# Sensors.net
KiCad netlist of a schematic drawn in Altium Designer
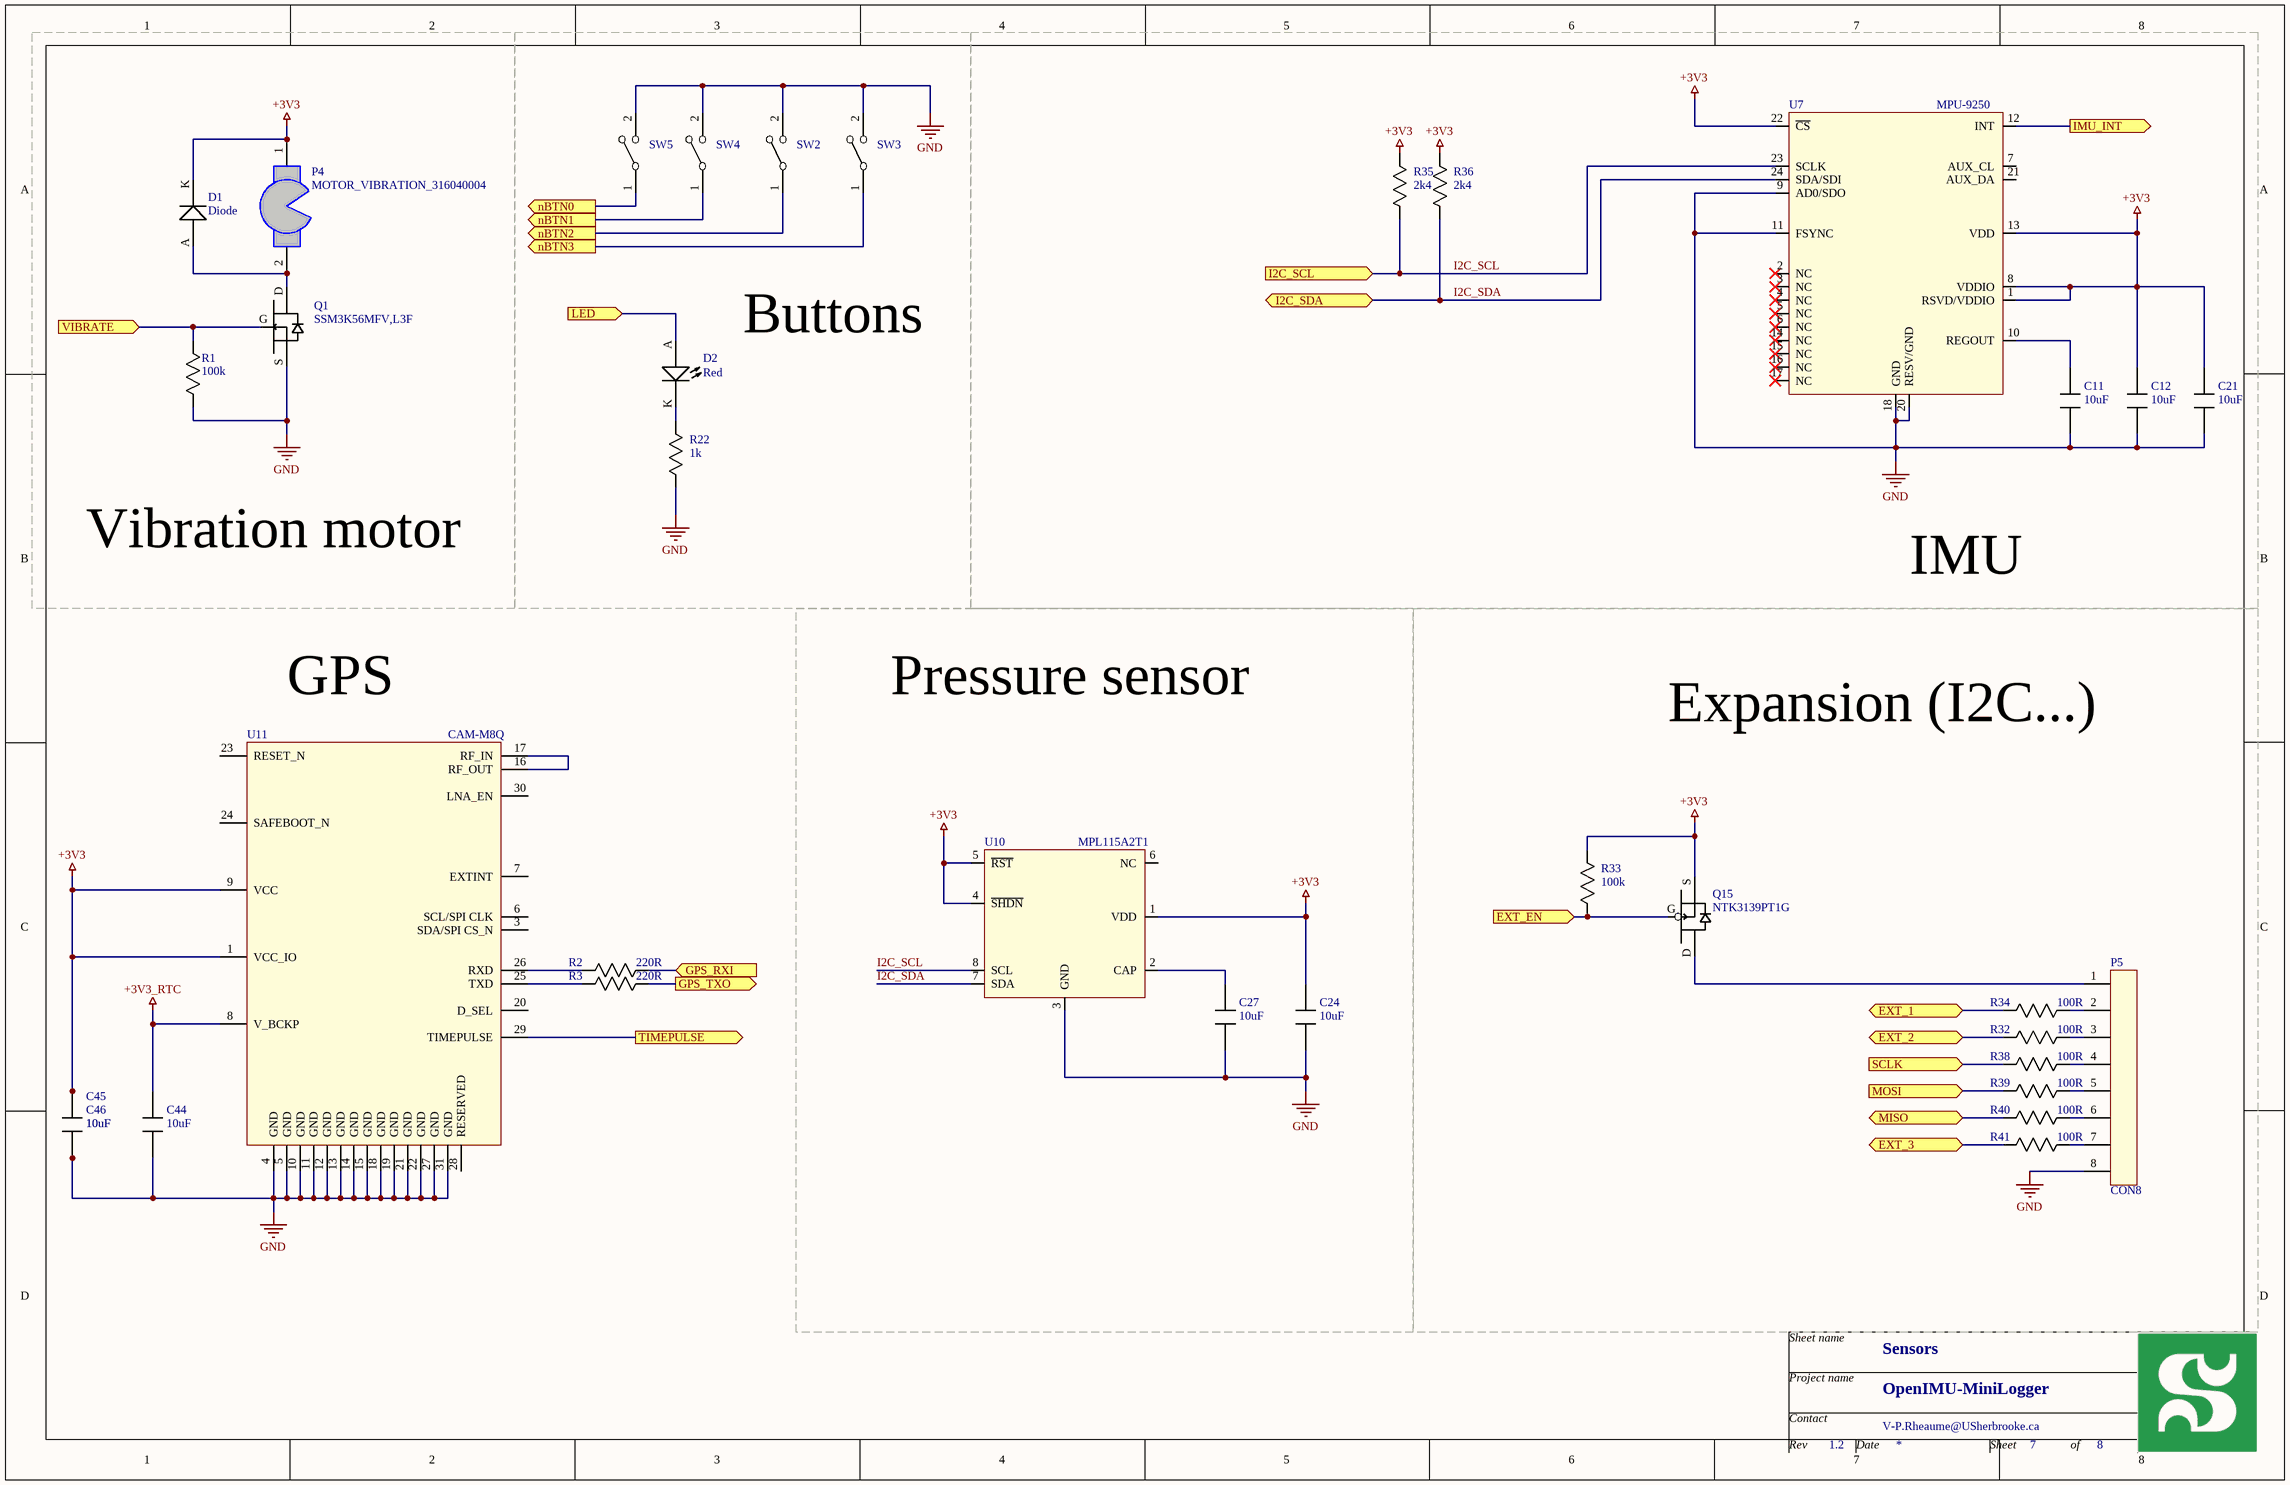
[diagram p0: Sensors.SchDoc]

(export (version "E")
  (design (tool "Eeschema 10.0.6"))
  (components
    (comp (ref "C11")
      (value "10uF")
      (footprint "0603")
      (description "Capacitor")
      (fields (field (name "MFG") "Murata"))
      (libsource (lib "INTER_2014") (part "Capacitor"))
    )
    (comp (ref "C12")
      (value "10uF")
      (footprint "0603")
      (description "Capacitor")
      (fields (field (name "MFG") "Murata"))
      (libsource (lib "INTER_2014") (part "Capacitor"))
    )
    (comp (ref "C21")
      (value "10uF")
      (footprint "0603")
      (description "Capacitor")
      (fields (field (name "MFG") "Murata"))
      (libsource (lib "INTER_2014") (part "Capacitor"))
    )
    (comp (ref "C24")
      (value "10uF")
      (footprint "0603")
      (description "Capacitor")
      (fields (field (name "MFG") "Murata"))
      (libsource (lib "INTER_2014") (part "Capacitor"))
    )
    (comp (ref "C27")
      (value "10uF")
      (footprint "0603")
      (description "Capacitor")
      (fields (field (name "MFG") "Murata"))
      (libsource (lib "INTER_2014") (part "Capacitor"))
    )
    (comp (ref "C44")
      (value "10uF")
      (footprint "0603")
      (description "Capacitor")
      (fields (field (name "MFG") "Murata"))
      (libsource (lib "INTER_2014") (part "Capacitor"))
    )
    (comp (ref "C45")
      (value "10uF")
      (footprint "0603")
      (description "Capacitor")
      (fields (field (name "MFG") "Murata"))
      (libsource (lib "INTER_2014") (part "Capacitor"))
    )
    (comp (ref "C46")
      (value "10uF")
      (footprint "0603")
      (description "Capacitor")
      (fields (field (name "MFG") "Murata"))
      (libsource (lib "INTER_2014") (part "Capacitor"))
    )
    (comp (ref "D1")
      (value "Diode")
      (footprint "DIODE_SOD523")
      (fields (field (name "MFG") "MCC"))
      (libsource (lib "INTER_2014") (part "Diode"))
    )
    (comp (ref "D2")
      (value "Red")
      (footprint "0805_LED")
      (description "LED")
      (fields (field (name "MFG") "Wurth") (field (name "Comment") "Diode_LED"))
      (libsource (lib "INTER_2014") (part "Diode_LED"))
    )
    (comp (ref "P4")
      (value "MOTOR_VIBRATION_316040004")
      (footprint "MOTOR_VIBRATION_316040004")
      (description "Round, flat, 10-mm diameter, 3-mm thick vibration motor")
      (fields (field (name "MFG") "Seeed"))
      (libsource (lib "INTER_2014") (part "MOTOR_VIBRATION_316040004"))
    )
    (comp (ref "P5")
      (value "CON8")
      (footprint "CONN8_JSTSH")
      (description "8-pins")
      (fields (field (name "MFG") "JST"))
      (libsource (lib "INTER_2014") (part "CON8"))
    )
    (comp (ref "Q1")
      (value "MOSFET_N_GDS")
      (footprint "SOT723")
      (description "NMOS")
      (fields (field (name "MFG") "Toshiba") (field (name "MFG_PN") "SSM3K56MFV,L3F"))
      (libsource (lib "INTER_2014") (part "MOSFET_N_GDS"))
    )
    (comp (ref "Q15")
      (value "MOSFET_P_GDS")
      (footprint "SOT723")
      (description "PMOS")
      (fields (field (name "MFG") "OnSemi") (field (name "MFG_PN") "NTK3139PT1G"))
      (libsource (lib "INTER_2014") (part "MOSFET_P_GDS"))
    )
    (comp (ref "R1")
      (value "100k")
      (footprint "0402")
      (description "Resistor")
      (fields (field (name "MFG") "Yageo"))
      (libsource (lib "INTER_2014") (part "Resistor"))
    )
    (comp (ref "R2")
      (value "220R")
      (footprint "0805")
      (description "Resistor")
      (fields (field (name "MFG") "Stackpole"))
      (libsource (lib "INTER_2014") (part "Resistor"))
    )
    (comp (ref "R3")
      (value "220R")
      (footprint "0805")
      (description "Resistor")
      (fields (field (name "MFG") "Stackpole"))
      (libsource (lib "INTER_2014") (part "Resistor"))
    )
    (comp (ref "R22")
      (value "1k")
      (footprint "0402")
      (description "Resistor")
      (fields (field (name "MFG") "TE"))
      (libsource (lib "INTER_2014") (part "Resistor"))
    )
    (comp (ref "R32")
      (value "100R")
      (footprint "0402")
      (description "Resistor")
      (fields (field (name "MFG") "TE"))
      (libsource (lib "INTER_2014") (part "Resistor"))
    )
    (comp (ref "R33")
      (value "100k")
      (footprint "0402")
      (description "Resistor")
      (fields (field (name "MFG") "Yageo"))
      (libsource (lib "INTER_2014") (part "Resistor"))
    )
    (comp (ref "R34")
      (value "100R")
      (footprint "0402")
      (description "Resistor")
      (fields (field (name "MFG") "TE"))
      (libsource (lib "INTER_2014") (part "Resistor"))
    )
    (comp (ref "R35")
      (value "2k4")
      (footprint "0402")
      (description "Resistor")
      (fields (field (name "MFG") "Yageo"))
      (libsource (lib "INTER_2014") (part "Resistor"))
    )
    (comp (ref "R36")
      (value "2k4")
      (footprint "0402")
      (description "Resistor")
      (fields (field (name "MFG") "Yageo"))
      (libsource (lib "INTER_2014") (part "Resistor"))
    )
    (comp (ref "R38")
      (value "100R")
      (footprint "0402")
      (description "Resistor")
      (fields (field (name "MFG") "TE"))
      (libsource (lib "INTER_2014") (part "Resistor"))
    )
    (comp (ref "R39")
      (value "100R")
      (footprint "0402")
      (description "Resistor")
      (fields (field (name "MFG") "TE"))
      (libsource (lib "INTER_2014") (part "Resistor"))
    )
    (comp (ref "R40")
      (value "100R")
      (footprint "0402")
      (description "Resistor")
      (fields (field (name "MFG") "TE"))
      (libsource (lib "INTER_2014") (part "Resistor"))
    )
    (comp (ref "R41")
      (value "100R")
      (footprint "0402")
      (description "Resistor")
      (fields (field (name "MFG") "TE"))
      (libsource (lib "INTER_2014") (part "Resistor"))
    )
    (comp (ref "SW2")
      (value "Button_2pins")
      (footprint "BUTTON_EVP-AW")
      (description "Button")
      (fields (field (name "MFG") "Panasonic"))
      (libsource (lib "INTER_2014") (part "Button_2pins"))
    )
    (comp (ref "SW3")
      (value "Button_2pins")
      (footprint "BUTTON_EVP-AW")
      (description "Button")
      (fields (field (name "MFG") "Panasonic"))
      (libsource (lib "INTER_2014") (part "Button_2pins"))
    )
    (comp (ref "SW4")
      (value "Button_2pins")
      (footprint "BUTTON_EVP-AW")
      (description "Button")
      (fields (field (name "MFG") "Panasonic"))
      (libsource (lib "INTER_2014") (part "Button_2pins"))
    )
    (comp (ref "SW5")
      (value "Button_2pins")
      (footprint "BUTTON_EVP-AW")
      (description "Button")
      (fields (field (name "MFG") "Panasonic"))
      (libsource (lib "INTER_2014") (part "Button_2pins"))
    )
    (comp (ref "U7")
      (value "MPU-9250")
      (footprint "QFN24-0.4mm-NOPAD")
      (description "IMU ACCEL/GYRO/MAG I2C/SPI 24QFN")
      (fields (field (name "MFG") "Invensense") (field (name "MFG_PN") "MPU-9250"))
      (libsource (lib "INTER_2014") (part "MPU-9250"))
    )
    (comp (ref "U10")
      (value "MPL115A2T1")
      (footprint "MPL115A2T1")
      (description "IC BAROMETER I2C")
      (fields (field (name "MFG") "NXP"))
      (libsource (lib "INTER_2014") (part "MPL115A2T1"))
    )
    (comp (ref "U11")
      (value "CAM-M8Q")
      (footprint "CAM-M8")
      (description "u-blox CAM GNSS antenna module")
      (fields (field (name "MFG") "u-blox"))
      (libsource (lib "INTER_2014") (part "CAM-M8"))
    )
  )
  (nets
    (net (code "1") (name "+3V3") (class "Default")
      (node (ref "C12") (pin "1") (pintype "passive"))
      (node (ref "C21") (pin "1") (pintype "passive"))
      (node (ref "C24") (pin "1") (pintype "passive"))
      (node (ref "C45") (pin "1") (pintype "passive"))
      (node (ref "C46") (pin "1") (pintype "passive"))
      (node (ref "D1") (pin "K") (pintype "passive"))
      (node (ref "P4") (pin "1") (pintype "passive"))
      (node (ref "Q15") (pin "S") (pintype "passive"))
      (node (ref "R33") (pin "2") (pintype "passive"))
      (node (ref "R35") (pin "1") (pintype "passive"))
      (node (ref "R36") (pin "1") (pintype "passive"))
      (node (ref "U10") (pin "1") (pinfunction "VDD_1") (pintype "passive"))
      (node (ref "U10") (pin "4") (pinfunction "~{SHDN}_4") (pintype "passive"))
      (node (ref "U10") (pin "5") (pinfunction "~{RST}_5") (pintype "passive"))
      (node (ref "U11") (pin "1") (pinfunction "VCC_IO_1") (pintype "passive"))
      (node (ref "U11") (pin "9") (pinfunction "VCC_9") (pintype "passive"))
      (node (ref "U7") (pin "1") (pinfunction "RSVD/VDDIO_1") (pintype "passive"))
      (node (ref "U7") (pin "13") (pinfunction "VDD_13") (pintype "passive"))
      (node (ref "U7") (pin "22") (pinfunction "~{CS}_22") (pintype "passive"))
      (node (ref "U7") (pin "8") (pinfunction "VDDIO_8") (pintype "passive"))
    )
    (net (code "2") (name "+3V3_RTC") (class "Default")
      (node (ref "C44") (pin "1") (pintype "passive"))
      (node (ref "U11") (pin "8") (pinfunction "V_BCKP_8") (pintype "passive"))
    )
    (net (code "3") (name "/EXT_1") (class "Default") (node (ref "R34") (pin "2") (pintype "passive")))
    (net (code "4") (name "/EXT_2") (class "Default") (node (ref "R32") (pin "2") (pintype "passive")))
    (net (code "5") (name "/EXT_3") (class "Default") (node (ref "R41") (pin "2") (pintype "passive")))
    (net (code "6") (name "/EXT_EN") (class "Default")
      (node (ref "Q15") (pin "G") (pintype "passive"))
      (node (ref "R33") (pin "1") (pintype "passive"))
    )
    (net (code "7") (name "/GPS_RXI") (class "Default") (node (ref "R2") (pin "1") (pintype "passive")))
    (net (code "8") (name "/GPS_TXO") (class "Default") (node (ref "R3") (pin "1") (pintype "passive")))
    (net (code "9") (name "/I2C_SCL") (class "Default")
      (node (ref "R35") (pin "2") (pintype "passive"))
      (node (ref "U10") (pin "8") (pinfunction "SCL_8") (pintype "passive"))
      (node (ref "U7") (pin "23") (pinfunction "SCLK_23") (pintype "passive"))
    )
    (net (code "10") (name "/I2C_SDA") (class "Default")
      (node (ref "R36") (pin "2") (pintype "passive"))
      (node (ref "U10") (pin "7") (pinfunction "SDA_7") (pintype "passive"))
      (node (ref "U7") (pin "24") (pinfunction "SDA/SDI_24") (pintype "passive"))
    )
    (net (code "11") (name "/IMU_INT") (class "Default")
      (node (ref "U7") (pin "12") (pinfunction "INT_12") (pintype "passive"))
    )
    (net (code "12") (name "/LED") (class "Default") (node (ref "D2") (pin "A") (pintype "passive")))
    (net (code "13") (name "/MISO") (class "Default") (node (ref "R40") (pin "2") (pintype "passive")))
    (net (code "14") (name "/MOSI") (class "Default") (node (ref "R39") (pin "2") (pintype "passive")))
    (net (code "15") (name "/SCLK") (class "Default") (node (ref "R38") (pin "2") (pintype "passive")))
    (net (code "16") (name "/TIMEPULSE") (class "Default")
      (node (ref "U11") (pin "29") (pinfunction "TIMEPULSE_29") (pintype "passive"))
    )
    (net (code "17") (name "/VIBRATE") (class "Default")
      (node (ref "Q1") (pin "G") (pintype "passive"))
      (node (ref "R1") (pin "1") (pintype "passive"))
    )
    (net (code "18") (name "/nBTN0") (class "Default") (node (ref "SW5") (pin "1") (pintype "passive")))
    (net (code "19") (name "/nBTN1") (class "Default") (node (ref "SW4") (pin "1") (pintype "passive")))
    (net (code "20") (name "/nBTN2") (class "Default") (node (ref "SW2") (pin "1") (pintype "passive")))
    (net (code "21") (name "/nBTN3") (class "Default") (node (ref "SW3") (pin "1") (pintype "passive")))
    (net (code "22") (name "GND") (class "Default")
      (node (ref "C11") (pin "2") (pintype "passive"))
      (node (ref "C12") (pin "2") (pintype "passive"))
      (node (ref "C21") (pin "2") (pintype "passive"))
      (node (ref "C24") (pin "2") (pintype "passive"))
      (node (ref "C27") (pin "2") (pintype "passive"))
      (node (ref "C44") (pin "2") (pintype "passive"))
      (node (ref "C45") (pin "2") (pintype "passive"))
      (node (ref "C46") (pin "2") (pintype "passive"))
      (node (ref "P5") (pin "8") (pintype "passive"))
      (node (ref "Q1") (pin "S") (pintype "passive"))
      (node (ref "R1") (pin "2") (pintype "passive"))
      (node (ref "R22") (pin "1") (pintype "passive"))
      (node (ref "SW2") (pin "2") (pintype "passive"))
      (node (ref "SW3") (pin "2") (pintype "passive"))
      (node (ref "SW4") (pin "2") (pintype "passive"))
      (node (ref "SW5") (pin "2") (pintype "passive"))
      (node (ref "U10") (pin "3") (pinfunction "GND_3") (pintype "passive"))
      (node (ref "U11") (pin "10") (pinfunction "GND_10") (pintype "passive"))
      (node (ref "U11") (pin "11") (pinfunction "GND_11") (pintype "passive"))
      (node (ref "U11") (pin "12") (pinfunction "GND_12") (pintype "passive"))
      (node (ref "U11") (pin "13") (pinfunction "GND_13") (pintype "passive"))
      (node (ref "U11") (pin "14") (pinfunction "GND_14") (pintype "passive"))
      (node (ref "U11") (pin "15") (pinfunction "GND_15") (pintype "passive"))
      (node (ref "U11") (pin "18") (pinfunction "GND_18") (pintype "passive"))
      (node (ref "U11") (pin "19") (pinfunction "GND_19") (pintype "passive"))
      (node (ref "U11") (pin "21") (pinfunction "GND_21") (pintype "passive"))
      (node (ref "U11") (pin "22") (pinfunction "GND_22") (pintype "passive"))
      (node (ref "U11") (pin "27") (pinfunction "GND_27") (pintype "passive"))
      (node (ref "U11") (pin "31") (pinfunction "GND_31") (pintype "passive"))
      (node (ref "U11") (pin "4") (pinfunction "GND_4") (pintype "passive"))
      (node (ref "U11") (pin "5") (pinfunction "GND_5") (pintype "passive"))
      (node (ref "U7") (pin "11") (pinfunction "FSYNC_11") (pintype "passive"))
      (node (ref "U7") (pin "18") (pinfunction "GND_18") (pintype "passive"))
      (node (ref "U7") (pin "20") (pinfunction "RESV/GND_20") (pintype "passive"))
      (node (ref "U7") (pin "9") (pinfunction "AD0/SDO_9") (pintype "passive"))
    )
    (net (code "23") (name "Net-(D1-PadA)") (class "Default")
      (node (ref "D1") (pin "A") (pintype "passive"))
      (node (ref "P4") (pin "2") (pintype "passive"))
      (node (ref "Q1") (pin "D") (pintype "passive"))
    )
    (net (code "24") (name "Net-(D2-PadK)") (class "Default")
      (node (ref "D2") (pin "K") (pintype "passive"))
      (node (ref "R22") (pin "2") (pintype "passive"))
    )
    (net (code "25") (name "Net-(P5-Pad1)") (class "Default")
      (node (ref "P5") (pin "1") (pintype "passive"))
      (node (ref "Q15") (pin "D") (pintype "passive"))
    )
    (net (code "26") (name "Net-(P5-Pad2)") (class "Default")
      (node (ref "P5") (pin "2") (pintype "passive"))
      (node (ref "R34") (pin "1") (pintype "passive"))
    )
    (net (code "27") (name "Net-(P5-Pad3)") (class "Default")
      (node (ref "P5") (pin "3") (pintype "passive"))
      (node (ref "R32") (pin "1") (pintype "passive"))
    )
    (net (code "28") (name "Net-(P5-Pad4)") (class "Default")
      (node (ref "P5") (pin "4") (pintype "passive"))
      (node (ref "R38") (pin "1") (pintype "passive"))
    )
    (net (code "29") (name "Net-(P5-Pad5)") (class "Default")
      (node (ref "P5") (pin "5") (pintype "passive"))
      (node (ref "R39") (pin "1") (pintype "passive"))
    )
    (net (code "30") (name "Net-(P5-Pad6)") (class "Default")
      (node (ref "P5") (pin "6") (pintype "passive"))
      (node (ref "R40") (pin "1") (pintype "passive"))
    )
    (net (code "31") (name "Net-(P5-Pad7)") (class "Default")
      (node (ref "P5") (pin "7") (pintype "passive"))
      (node (ref "R41") (pin "1") (pintype "passive"))
    )
    (net (code "32") (name "Net-(U7-REGOUT)") (class "Default")
      (node (ref "C11") (pin "1") (pintype "passive"))
      (node (ref "U7") (pin "10") (pinfunction "REGOUT_10") (pintype "passive"))
    )
    (net (code "33") (name "Net-(U10-CAP)") (class "Default")
      (node (ref "C27") (pin "1") (pintype "passive"))
      (node (ref "U10") (pin "2") (pinfunction "CAP_2") (pintype "passive"))
    )
    (net (code "34") (name "Net-(U11-RF_IN)") (class "Default")
      (node (ref "U11") (pin "16") (pinfunction "RF_OUT_16") (pintype "passive"))
      (node (ref "U11") (pin "17") (pinfunction "RF_IN_17") (pintype "passive"))
    )
    (net (code "35") (name "Net-(U11-RXD)") (class "Default")
      (node (ref "R2") (pin "2") (pintype "passive"))
      (node (ref "U11") (pin "26") (pinfunction "RXD_26") (pintype "passive"))
    )
    (net (code "36") (name "Net-(U11-TXD)") (class "Default")
      (node (ref "R3") (pin "2") (pintype "passive"))
      (node (ref "U11") (pin "25") (pinfunction "TXD_25") (pintype "passive"))
    )
    (net (code "37") (name "unconnected-(U7-AUX_CL-Pad7)") (class "Default")
      (node (ref "U7") (pin "7") (pinfunction "AUX_CL_7") (pintype "passive"))
    )
    (net (code "38") (name "unconnected-(U7-AUX_DA-Pad21)") (class "Default")
      (node (ref "U7") (pin "21") (pinfunction "AUX_DA_21") (pintype "passive"))
    )
    (net (code "39") (name "unconnected-(U7-NC-Pad2)") (class "Default")
      (node (ref "U7") (pin "2") (pinfunction "NC_2") (pintype "passive+no_connect"))
    )
    (net (code "40") (name "unconnected-(U7-NC-Pad3)") (class "Default")
      (node (ref "U7") (pin "3") (pinfunction "NC_3") (pintype "passive+no_connect"))
    )
    (net (code "41") (name "unconnected-(U7-NC-Pad4)") (class "Default")
      (node (ref "U7") (pin "4") (pinfunction "NC_4") (pintype "passive+no_connect"))
    )
    (net (code "42") (name "unconnected-(U7-NC-Pad5)") (class "Default")
      (node (ref "U7") (pin "5") (pinfunction "NC_5") (pintype "passive+no_connect"))
    )
    (net (code "43") (name "unconnected-(U7-NC-Pad6)") (class "Default")
      (node (ref "U7") (pin "6") (pinfunction "NC_6") (pintype "passive+no_connect"))
    )
    (net (code "44") (name "unconnected-(U7-NC-Pad14)") (class "Default")
      (node (ref "U7") (pin "14") (pinfunction "NC_14") (pintype "passive+no_connect"))
    )
    (net (code "45") (name "unconnected-(U7-NC-Pad15)") (class "Default")
      (node (ref "U7") (pin "15") (pinfunction "NC_15") (pintype "passive+no_connect"))
    )
    (net (code "46") (name "unconnected-(U7-NC-Pad16)") (class "Default")
      (node (ref "U7") (pin "16") (pinfunction "NC_16") (pintype "passive+no_connect"))
    )
    (net (code "47") (name "unconnected-(U7-NC-Pad17)") (class "Default")
      (node (ref "U7") (pin "17") (pinfunction "NC_17") (pintype "passive+no_connect"))
    )
    (net (code "48") (name "unconnected-(U7-RESV{slash}NC-Pad19)") (class "Default")
      (node (ref "U7") (pin "19") (pinfunction "RESV/NC_19") (pintype "passive"))
    )
    (net (code "49") (name "unconnected-(U10-NC-Pad6)") (class "Default")
      (node (ref "U10") (pin "6") (pinfunction "NC_6") (pintype "passive"))
    )
    (net (code "50") (name "unconnected-(U11-D_SEL-Pad20)") (class "Default")
      (node (ref "U11") (pin "20") (pinfunction "D_SEL_20") (pintype "passive"))
    )
    (net (code "51") (name "unconnected-(U11-EXTINT-Pad7)") (class "Default")
      (node (ref "U11") (pin "7") (pinfunction "EXTINT_7") (pintype "passive"))
    )
    (net (code "52") (name "unconnected-(U11-LNA_EN-Pad30)") (class "Default")
      (node (ref "U11") (pin "30") (pinfunction "LNA_EN_30") (pintype "passive"))
    )
    (net (code "53") (name "unconnected-(U11-RESERVED-Pad2)") (class "Default")
      (node (ref "U11") (pin "2") (pinfunction "RESERVED_2") (pintype "passive"))
    )
    (net (code "54") (name "unconnected-(U11-RESERVED-Pad28)") (class "Default")
      (node (ref "U11") (pin "28") (pinfunction "RESERVED_28") (pintype "passive"))
    )
    (net (code "55") (name "unconnected-(U11-RESET_N-Pad23)") (class "Default")
      (node (ref "U11") (pin "23") (pinfunction "RESET_N_23") (pintype "passive"))
    )
    (net (code "56") (name "unconnected-(U11-SAFEBOOT_N-Pad24)") (class "Default")
      (node (ref "U11") (pin "24") (pinfunction "SAFEBOOT_N_24") (pintype "passive"))
    )
    (net (code "57") (name "unconnected-(U11-SCL{slash}SPI_CLK-Pad6)") (class "Default")
      (node (ref "U11") (pin "6") (pinfunction "SCL/SPI_CLK_6") (pintype "passive"))
    )
    (net (code "58") (name "unconnected-(U11-SDA{slash}SPI_CS_N-Pad3)") (class "Default")
      (node (ref "U11") (pin "3") (pinfunction "SDA/SPI_CS_N_3") (pintype "passive"))
    )
  )
)
